# AC_voltage_read.net
KiCad netlist of a schematic drawn in EAGLE
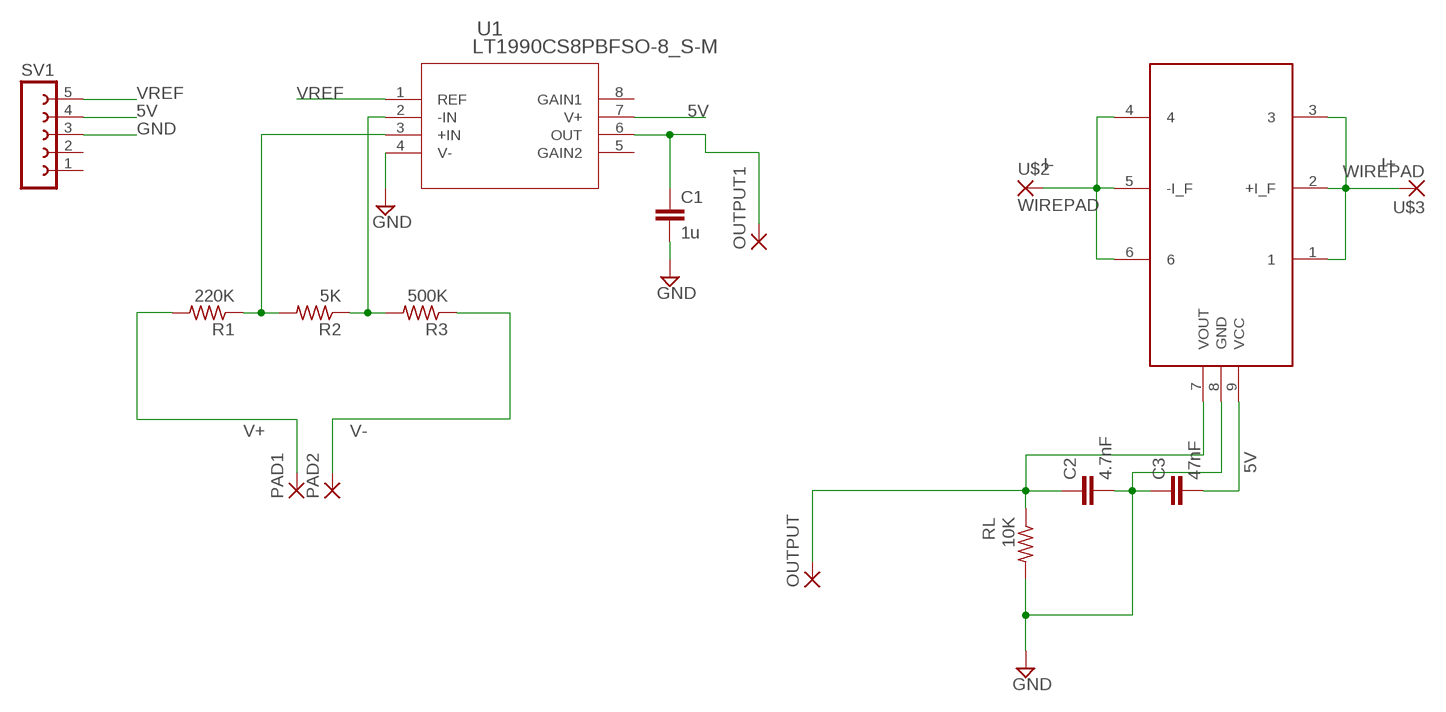
[diagram p0: schematic, sheet 1]

(export (version "E")
  (design (tool "Eeschema 10.0.6"))
  (components
    (comp (ref "C1")
      (value "1u")
      (footprint "eagle-import:C075-032X103")
      (libsource (lib "eagle-import") (part "C-EU075-032X103"))
    )
    (comp (ref "C2")
      (value "4.7nF")
      (footprint "eagle-import:C050-045X075")
      (libsource (lib "eagle-import") (part "C-EU050-045X075"))
    )
    (comp (ref "C3")
      (value "47nF")
      (footprint "eagle-import:C050-045X075")
      (libsource (lib "eagle-import") (part "C-EU050-045X075"))
    )
    (comp (ref "OUTPUT")
      (value "WIREPAD3,17/1,2")
      (footprint "eagle-import:3,17_1,2")
      (libsource (lib "eagle-import") (part "WIREPAD3,17/1,2"))
    )
    (comp (ref "OUTPUT1")
      (value "WIREPAD3,17/1,2")
      (footprint "eagle-import:3,17_1,2")
      (libsource (lib "eagle-import") (part "WIREPAD3,17/1,2"))
    )
    (comp (ref "PAD1")
      (value "3,81/1,1")
      (footprint "eagle-import:3,81_1,1")
      (libsource (lib "eagle-import") (part "3,81/1,1"))
    )
    (comp (ref "PAD2")
      (value "3,81/1,1")
      (footprint "eagle-import:3,81_1,1")
      (libsource (lib "eagle-import") (part "3,81/1,1"))
    )
    (comp (ref "R1")
      (value "220K")
      (footprint "eagle-import:0207_12")
      (libsource (lib "eagle-import") (part "R-US_0207/12"))
    )
    (comp (ref "R2")
      (value "5K")
      (footprint "eagle-import:0207_12")
      (libsource (lib "eagle-import") (part "R-US_0207/12"))
    )
    (comp (ref "R3")
      (value "500K")
      (footprint "eagle-import:0207_12")
      (libsource (lib "eagle-import") (part "R-US_0207/12"))
    )
    (comp (ref "RL")
      (value "10K")
      (footprint "eagle-import:0207_12")
      (libsource (lib "eagle-import") (part "R-US_0207/12"))
    )
    (comp (ref "SV1")
      (value "FE05-1")
      (footprint "eagle-import:FE05-1")
      (libsource (lib "eagle-import") (part "FE05-1"))
    )
    (comp (ref "U$1")
      (value "S22P015S05")
      (footprint "eagle-import:S22FOOTPRINT")
      (libsource (lib "eagle-import") (part "S22P015S05"))
    )
    (comp (ref "U$2")
      (value "WIREPAD")
      (footprint "eagle-import:WIREPAD")
      (libsource (lib "eagle-import") (part "WIREPAD"))
    )
    (comp (ref "U$3")
      (value "WIREPAD")
      (footprint "eagle-import:WIREPAD")
      (libsource (lib "eagle-import") (part "WIREPAD"))
    )
    (comp (ref "U1")
      (value "LT1990CS8PBFSO-8_S-M")
      (footprint "eagle-import:SO-8_S-M")
      (fields (field (name "MANUFACTURER_PART_NUMBER") "lt1990cs8#pbf"))
      (libsource (lib "eagle-import") (part "LT1990CS8PBFSO-8_S-M"))
    )
  )
  (nets
    (net (code "1") (name "/5V") (class "Default")
      (node (ref "C3") (pin "2") (pinfunction "2_2") (pintype "passive"))
      (node (ref "SV1") (pin "4") (pinfunction "4_4") (pintype "passive"))
      (node (ref "U$1") (pin "9") (pinfunction "VCC_9") (pintype "bidirectional"))
      (node (ref "U1") (pin "7") (pinfunction "V+_7") (pintype "power_in"))
    )
    (net (code "2") (name "/I+") (class "Default")
      (node (ref "U$1") (pin "1") (pinfunction "1_1") (pintype "bidirectional"))
      (node (ref "U$1") (pin "2") (pinfunction "+I_F_2") (pintype "bidirectional"))
      (node (ref "U$1") (pin "3") (pinfunction "3_3") (pintype "bidirectional"))
      (node (ref "U$3") (pin "P$1") (pinfunction "P_P$1") (pintype "passive"))
    )
    (net (code "3") (name "/I-") (class "Default")
      (node (ref "U$1") (pin "4") (pinfunction "4_4") (pintype "bidirectional"))
      (node (ref "U$1") (pin "5") (pinfunction "-I_F_5") (pintype "bidirectional"))
      (node (ref "U$1") (pin "6") (pinfunction "6_6") (pintype "bidirectional"))
      (node (ref "U$2") (pin "P$1") (pinfunction "P_P$1") (pintype "passive"))
    )
    (net (code "4") (name "/V+") (class "Default")
      (node (ref "PAD1") (pin "1") (pinfunction "P_1") (pintype "passive"))
      (node (ref "R1") (pin "2") (pinfunction "2_2") (pintype "passive"))
    )
    (net (code "5") (name "/V-") (class "Default")
      (node (ref "PAD2") (pin "1") (pinfunction "P_1") (pintype "passive"))
      (node (ref "R3") (pin "1") (pinfunction "1_1") (pintype "passive"))
    )
    (net (code "6") (name "/VREF") (class "Default")
      (node (ref "SV1") (pin "5") (pinfunction "5_5") (pintype "passive"))
      (node (ref "U1") (pin "1") (pinfunction "REF_1") (pintype "input"))
    )
    (net (code "7") (name "GND") (class "Default")
      (node (ref "C1") (pin "2") (pinfunction "2_2") (pintype "passive"))
      (node (ref "C2") (pin "2") (pinfunction "2_2") (pintype "passive"))
      (node (ref "C3") (pin "1") (pinfunction "1_1") (pintype "passive"))
      (node (ref "RL") (pin "2") (pinfunction "2_2") (pintype "passive"))
      (node (ref "SV1") (pin "3") (pinfunction "3_3") (pintype "passive"))
      (node (ref "U$1") (pin "8") (pinfunction "GND_8") (pintype "bidirectional"))
      (node (ref "U1") (pin "4") (pinfunction "V-_4") (pintype "power_in"))
    )
    (net (code "8") (name "Net-(OUTPUT-P)") (class "Default")
      (node (ref "C2") (pin "1") (pinfunction "1_1") (pintype "passive"))
      (node (ref "OUTPUT") (pin "1") (pinfunction "P_1") (pintype "passive"))
      (node (ref "RL") (pin "1") (pinfunction "1_1") (pintype "passive"))
      (node (ref "U$1") (pin "7") (pinfunction "VOUT_7") (pintype "bidirectional"))
    )
    (net (code "9") (name "Net-(OUTPUT1-P)") (class "Default")
      (node (ref "C1") (pin "1") (pinfunction "1_1") (pintype "passive"))
      (node (ref "OUTPUT1") (pin "1") (pinfunction "P_1") (pintype "passive"))
      (node (ref "U1") (pin "6") (pinfunction "OUT_6") (pintype "output"))
    )
    (net (code "10") (name "Net-(U1-+IN)") (class "Default")
      (node (ref "R1") (pin "1") (pinfunction "1_1") (pintype "passive"))
      (node (ref "R2") (pin "2") (pinfunction "2_2") (pintype "passive"))
      (node (ref "U1") (pin "3") (pinfunction "+IN_3") (pintype "input"))
    )
    (net (code "11") (name "Net-(U1--IN)") (class "Default")
      (node (ref "R2") (pin "1") (pinfunction "1_1") (pintype "passive"))
      (node (ref "R3") (pin "2") (pinfunction "2_2") (pintype "passive"))
      (node (ref "U1") (pin "2") (pinfunction "-IN_2") (pintype "input"))
    )
    (net (code "12") (name "unconnected-(SV1-Pad1)") (class "Default")
      (node (ref "SV1") (pin "1") (pinfunction "1_1") (pintype "passive"))
    )
    (net (code "13") (name "unconnected-(SV1-Pad2)") (class "Default")
      (node (ref "SV1") (pin "2") (pinfunction "2_2") (pintype "passive"))
    )
    (net (code "14") (name "unconnected-(U1-GAIN1-Pad8)") (class "Default")
      (node (ref "U1") (pin "8") (pinfunction "GAIN1_8") (pintype "input"))
    )
    (net (code "15") (name "unconnected-(U1-GAIN2-Pad5)") (class "Default")
      (node (ref "U1") (pin "5") (pinfunction "GAIN2_5") (pintype "input"))
    )
  )
)
